# Schematics.net
KiCad netlist of a schematic drawn in EAGLE
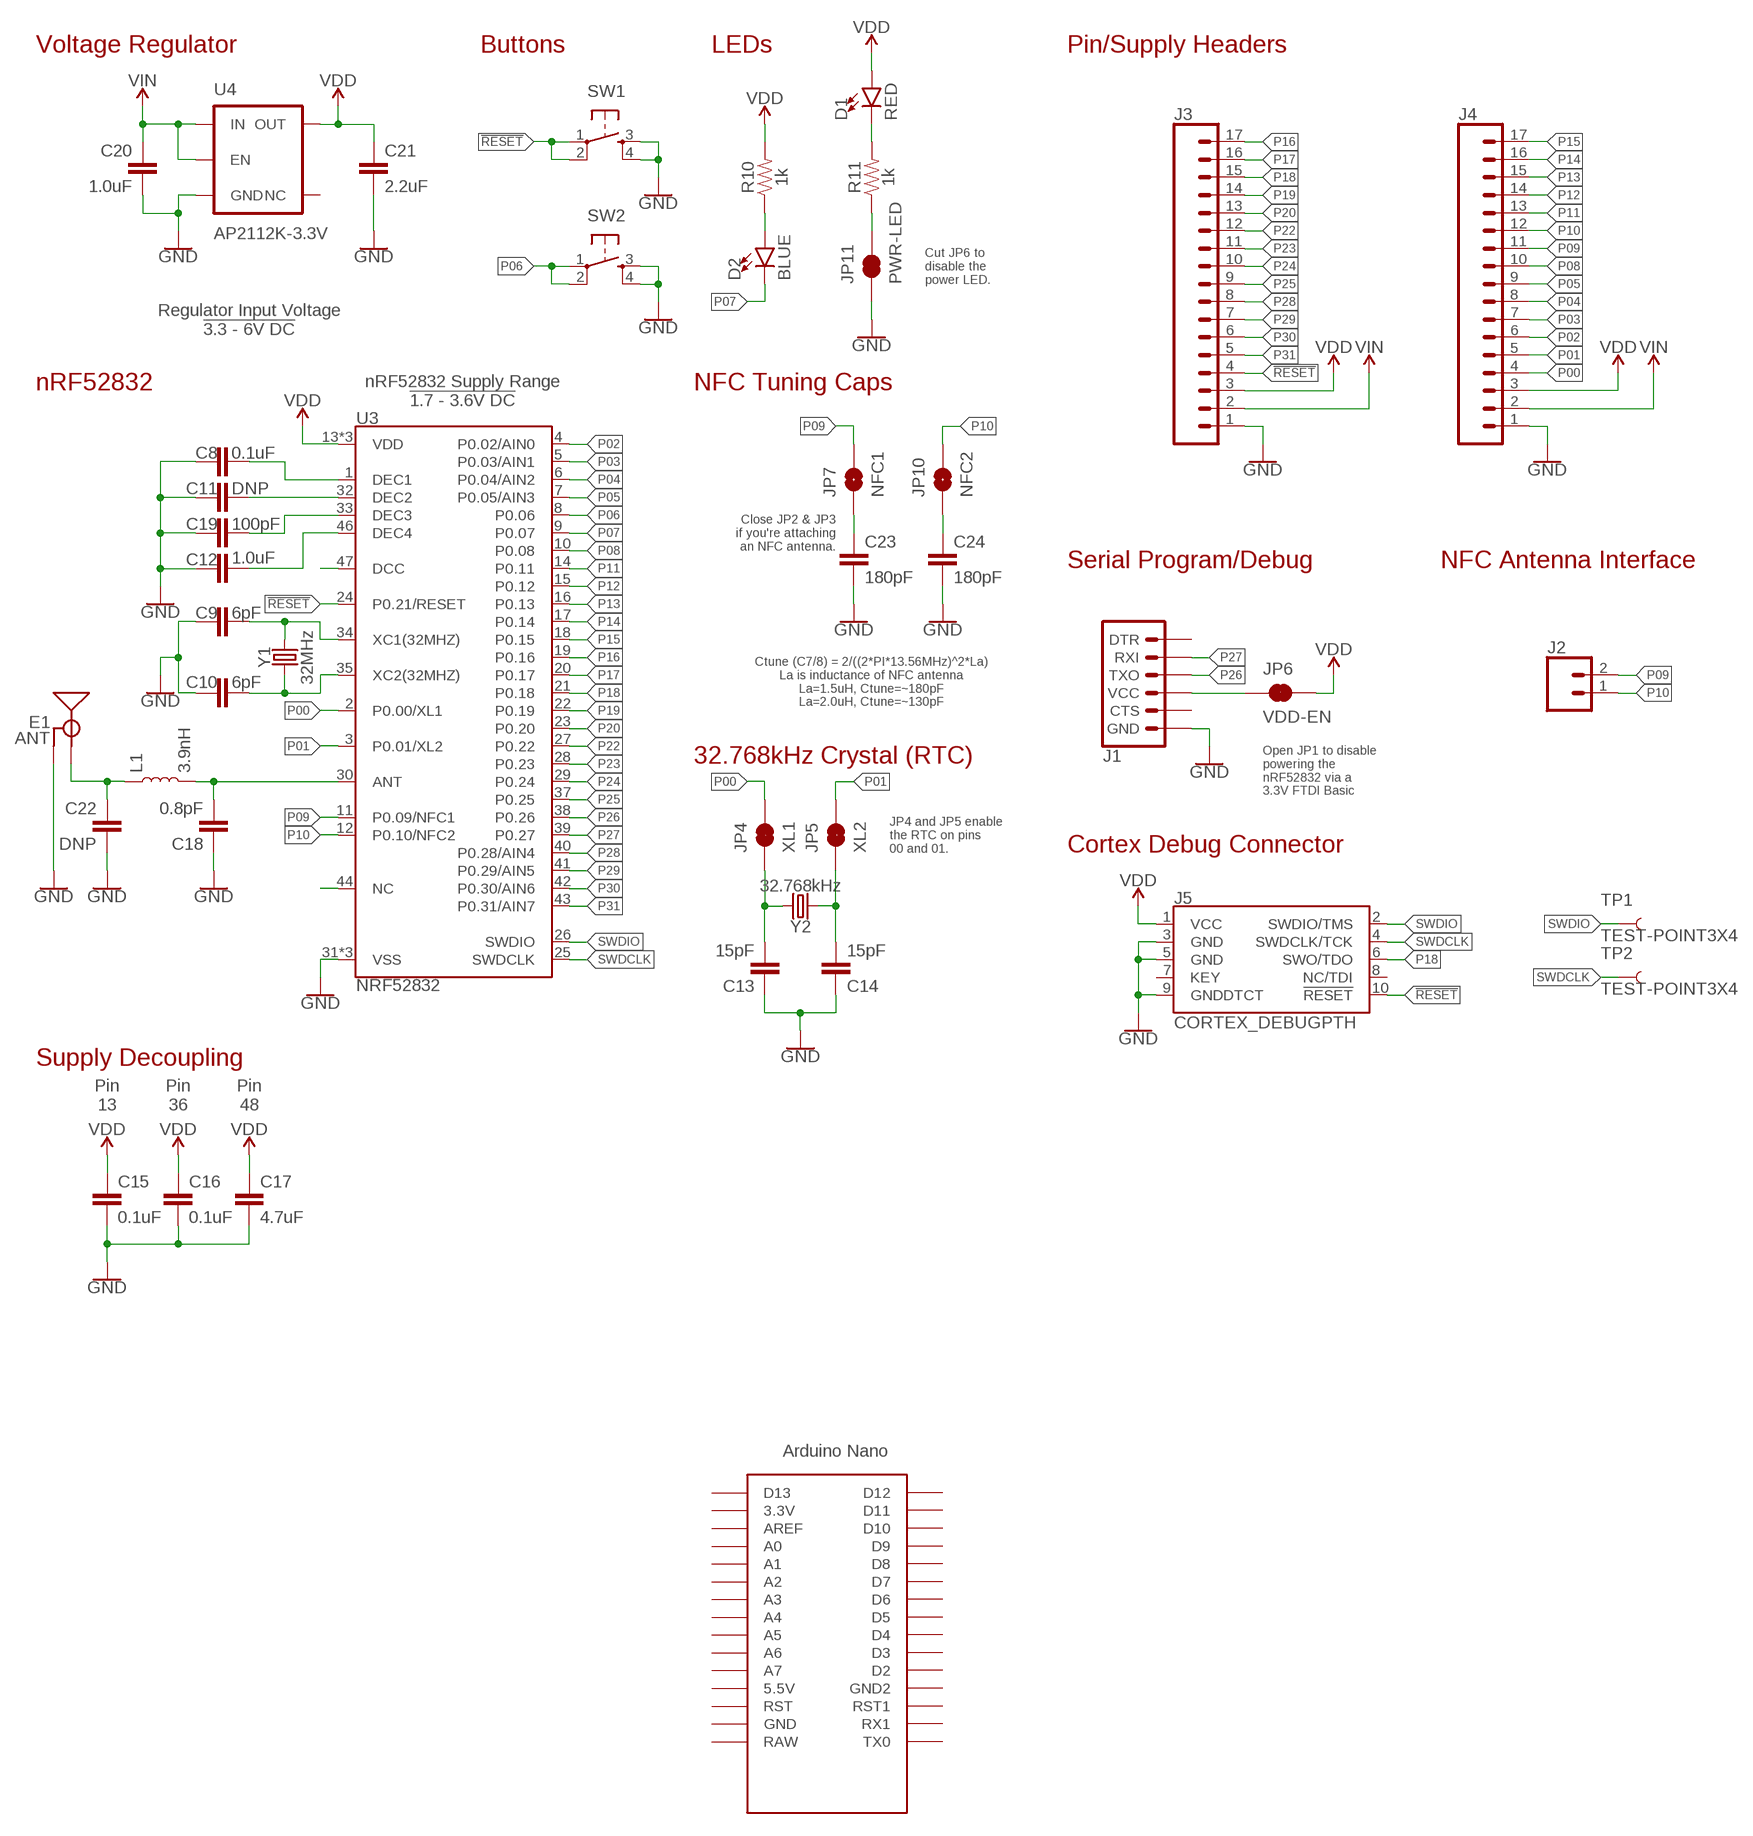
[diagram p0: schematic, sheet 1, part 1 of 2]
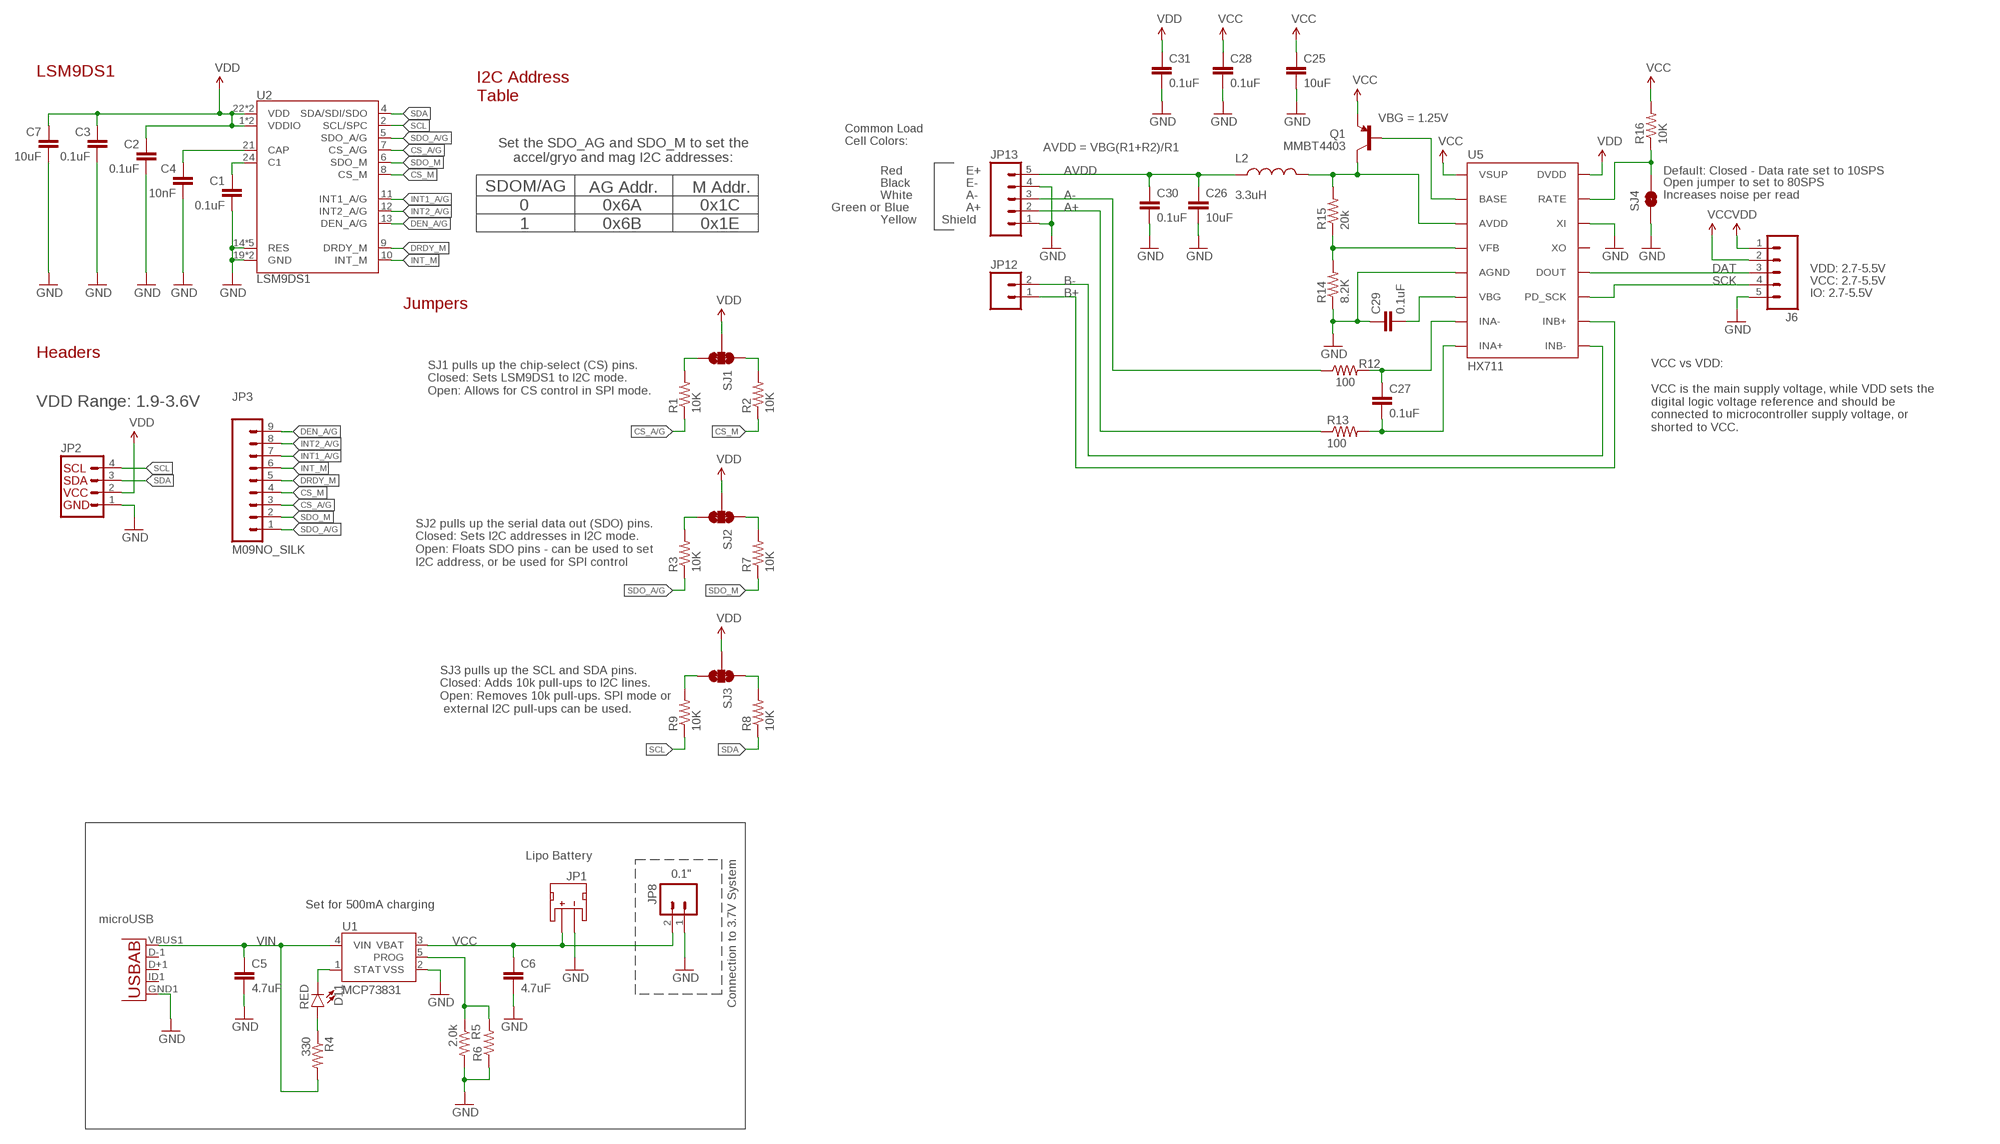
[diagram p1: schematic, sheet 1, part 2 of 2]

(export (version "E")
  (design (tool "Eeschema 10.0.6"))
  (components
    (comp (ref "C1")
      (value "0.1uF")
      (footprint "eagle-import:0603-CAP@1")
      (libsource (lib "eagle-import") (part "0.1UF-25V(+80/-20%)(0603)"))
    )
    (comp (ref "C2")
      (value "0.1uF")
      (footprint "eagle-import:0603-CAP@1")
      (libsource (lib "eagle-import") (part "0.1UF-25V(+80/-20%)(0603)"))
    )
    (comp (ref "C3")
      (value "0.1uF")
      (footprint "eagle-import:0603-CAP@1")
      (libsource (lib "eagle-import") (part "0.1UF-25V(+80/-20%)(0603)"))
    )
    (comp (ref "C4")
      (value "10nF")
      (footprint "eagle-import:0603-CAP@1")
      (libsource (lib "eagle-import") (part "10NF/10000PF-50V-10%(0603)"))
    )
    (comp (ref "C5")
      (value "4.7uF")
      (footprint "eagle-import:0603-CAP@1")
      (libsource (lib "eagle-import") (part "4.7UF-6.3V-10%(0603)0603"))
    )
    (comp (ref "C6")
      (value "4.7uF")
      (footprint "eagle-import:0603-CAP@1")
      (libsource (lib "eagle-import") (part "4.7UF-6.3V-10%(0603)0603"))
    )
    (comp (ref "C7")
      (value "10uF")
      (footprint "eagle-import:0603-CAP@1")
      (libsource (lib "eagle-import") (part "10UF-6.3V-20%(0603)"))
    )
    (comp (ref "C8")
      (value "0.1uF")
      (footprint "eagle-import:0402")
      (libsource (lib "eagle-import") (part "0.1UF-0402-16V-10%"))
    )
    (comp (ref "C9")
      (value "6pF")
      (footprint "eagle-import:0402")
      (libsource (lib "eagle-import") (part "6PF-0402-50V-0.5%"))
    )
    (comp (ref "C10")
      (value "6pF")
      (footprint "eagle-import:0402")
      (libsource (lib "eagle-import") (part "6PF-0402-50V-0.5%"))
    )
    (comp (ref "C11")
      (value "DNP")
      (footprint "eagle-import:0402")
      (libsource (lib "eagle-import") (part "CAP0402"))
    )
    (comp (ref "C12")
      (value "1.0uF")
      (footprint "eagle-import:0402")
      (libsource (lib "eagle-import") (part "1.0UF-0402-16V-10%"))
    )
    (comp (ref "C13")
      (value "15pF")
      (footprint "eagle-import:0402")
      (libsource (lib "eagle-import") (part "15PF-0402-50V-5%"))
    )
    (comp (ref "C14")
      (value "15pF")
      (footprint "eagle-import:0402")
      (libsource (lib "eagle-import") (part "15PF-0402-50V-5%"))
    )
    (comp (ref "C15")
      (value "0.1uF")
      (footprint "eagle-import:0402")
      (libsource (lib "eagle-import") (part "0.1UF-0402-16V-10%"))
    )
    (comp (ref "C16")
      (value "0.1uF")
      (footprint "eagle-import:0402")
      (libsource (lib "eagle-import") (part "0.1UF-0402-16V-10%"))
    )
    (comp (ref "C17")
      (value "4.7uF")
      (footprint "eagle-import:0603")
      (libsource (lib "eagle-import") (part "4.7UF0603"))
    )
    (comp (ref "C18")
      (value "0.8pF")
      (footprint "eagle-import:0402")
      (libsource (lib "eagle-import") (part "0.8PF-0402-50V-0.1PF"))
    )
    (comp (ref "C19")
      (value "100pF")
      (footprint "eagle-import:0402")
      (libsource (lib "eagle-import") (part "100PF-0402-50V-5%"))
    )
    (comp (ref "C20")
      (value "1.0uF")
      (footprint "eagle-import:0603")
      (libsource (lib "eagle-import") (part "1.0UF-0603-16V-10%"))
    )
    (comp (ref "C21")
      (value "2.2uF")
      (footprint "eagle-import:0603")
      (libsource (lib "eagle-import") (part "2.2UF-0603-10V-20%"))
    )
    (comp (ref "C22")
      (value "DNP")
      (footprint "eagle-import:0402")
      (libsource (lib "eagle-import") (part "CAP0402"))
    )
    (comp (ref "C23")
      (value "180pF")
      (footprint "eagle-import:0603")
      (libsource (lib "eagle-import") (part "180PF-0603-50V-5%"))
    )
    (comp (ref "C24")
      (value "180pF")
      (footprint "eagle-import:0603")
      (libsource (lib "eagle-import") (part "180PF-0603-50V-5%"))
    )
    (comp (ref "C25")
      (value "10uF")
      (footprint "eagle-import:1210")
      (libsource (lib "eagle-import") (part "10UF50V20%(1210)"))
    )
    (comp (ref "C26")
      (value "10uF")
      (footprint "eagle-import:1210")
      (libsource (lib "eagle-import") (part "10UF50V20%(1210)"))
    )
    (comp (ref "C27")
      (value "0.1uF")
      (footprint "eagle-import:0603-CAP")
      (libsource (lib "eagle-import") (part "0.1UF-25V-5%(0603)"))
    )
    (comp (ref "C28")
      (value "0.1uF")
      (footprint "eagle-import:0603-CAP")
      (libsource (lib "eagle-import") (part "0.1UF-25V-5%(0603)"))
    )
    (comp (ref "C29")
      (value "0.1uF")
      (footprint "eagle-import:0603-CAP")
      (libsource (lib "eagle-import") (part "0.1UF-25V-5%(0603)"))
    )
    (comp (ref "C30")
      (value "0.1uF")
      (footprint "eagle-import:0603-CAP")
      (libsource (lib "eagle-import") (part "0.1UF-25V-5%(0603)"))
    )
    (comp (ref "C31")
      (value "0.1uF")
      (footprint "eagle-import:0603-CAP")
      (libsource (lib "eagle-import") (part "0.1UF-25V-5%(0603)"))
    )
    (comp (ref "D1")
      (value "RED")
      (footprint "eagle-import:LED-0603")
      (libsource (lib "eagle-import") (part "LED-RED0603"))
    )
    (comp (ref "D2")
      (value "BLUE")
      (footprint "eagle-import:LED-0603")
      (libsource (lib "eagle-import") (part "LED-BLUE0603"))
    )
    (comp (ref "D11")
      (value "RED")
      (footprint "eagle-import:LED-0603")
      (libsource (lib "eagle-import") (part "LED-RED0603"))
    )
    (comp (ref "E1")
      (value "ANT")
      (footprint "eagle-import:TRACE_ANTENNA_2.4GHZ_15.2MM")
      (libsource (lib "eagle-import") (part "ANTENNA-GROUNDEDTRACE-15.2MM"))
    )
    (comp (ref "J1")
      (value "ARDUINO_SERIAL_PROGRAMPTH")
      (footprint "eagle-import:1X06")
      (libsource (lib "eagle-import") (part "ARDUINO_SERIAL_PROGRAMPTH"))
    )
    (comp (ref "J2")
      (value "CONN_02PTH")
      (footprint "eagle-import:1X02@2")
      (libsource (lib "eagle-import") (part "CONN_02PTH"))
    )
    (comp (ref "J3")
      (value "CONN_17")
      (footprint "eagle-import:1X17")
      (libsource (lib "eagle-import") (part "CONN_17"))
    )
    (comp (ref "J4")
      (value "CONN_17")
      (footprint "eagle-import:1X17")
      (libsource (lib "eagle-import") (part "CONN_17"))
    )
    (comp (ref "J5")
      (value "CORTEX_DEBUGPTH")
      (footprint "eagle-import:2X5-PTH-1.27MM")
      (libsource (lib "eagle-import") (part "CORTEX_DEBUGPTH"))
    )
    (comp (ref "J6")
      (value "M05PTH")
      (footprint "eagle-import:1X05")
      (libsource (lib "eagle-import") (part "M05PTH"))
    )
    (comp (ref "JP1")
      (value "JST")
      (footprint "eagle-import:JST-2-SMD@1")
      (libsource (lib "eagle-import") (part "JST_2MM_MALE"))
    )
    (comp (ref "JP2")
      (value "I2C_STANDARD_NO_SILK")
      (footprint "eagle-import:1X04_NO_SILK")
      (libsource (lib "eagle-import") (part "I2C_STANDARD_NO_SILK"))
    )
    (comp (ref "JP3")
      (value "M09NO_SILK")
      (footprint "eagle-import:1X09_NO_SILK")
      (libsource (lib "eagle-import") (part "M09NO_SILK"))
    )
    (comp (ref "JP4")
      (value "XL1")
      (footprint "eagle-import:PAD-JUMPER-2-NC_BY_TRACE_YES_SILK")
      (libsource (lib "eagle-import") (part "JUMPER-PAD-2-NC_BY_TRACE"))
    )
    (comp (ref "JP5")
      (value "XL2")
      (footprint "eagle-import:PAD-JUMPER-2-NC_BY_TRACE_YES_SILK")
      (libsource (lib "eagle-import") (part "JUMPER-PAD-2-NC_BY_TRACE"))
    )
    (comp (ref "JP6")
      (value "VDD-EN")
      (footprint "eagle-import:SMT-JUMPER_2_NC_TRACE_SILK")
      (libsource (lib "eagle-import") (part "JUMPER-SMT_2_NC_TRACE_SILK"))
    )
    (comp (ref "JP7")
      (value "NFC1")
      (footprint "eagle-import:SMT-JUMPER_2_NO_SILK")
      (libsource (lib "eagle-import") (part "JUMPER-SMT_2_NO_SILK"))
    )
    (comp (ref "JP8")
      (value "M02PTH")
      (footprint "eagle-import:1X02")
      (libsource (lib "eagle-import") (part "M02PTH"))
    )
    (comp (ref "JP9")
      (value "Micro USB")
      (footprint "eagle-import:USB-AB-MICRO-SMD_V03")
      (libsource (lib "eagle-import") (part "USB-ABCONN-11794"))
    )
    (comp (ref "JP10")
      (value "NFC2")
      (footprint "eagle-import:SMT-JUMPER_2_NO_SILK")
      (libsource (lib "eagle-import") (part "JUMPER-SMT_2_NO_SILK"))
    )
    (comp (ref "JP11")
      (value "PWR-LED")
      (footprint "eagle-import:PAD-JUMPER-2-NC_BY_TRACE_YES_SILK")
      (libsource (lib "eagle-import") (part "JUMPER-PAD-2-NC_BY_TRACE"))
    )
    (comp (ref "JP12")
      (value "M02PTH")
      (footprint "eagle-import:1X02")
      (libsource (lib "eagle-import") (part "M02PTH"))
    )
    (comp (ref "JP13")
      (value "M05PTH")
      (footprint "eagle-import:1X05")
      (libsource (lib "eagle-import") (part "M05PTH"))
    )
    (comp (ref "L1")
      (value "3.9nH")
      (footprint "eagle-import:0402")
      (libsource (lib "eagle-import") (part "INDUCTOR-0402-3.9NH"))
    )
    (comp (ref "L2")
      (value "3.3uH")
      (footprint "eagle-import:0805")
      (libsource (lib "eagle-import") (part "INDUCTOR0805-IND"))
    )
    (comp (ref "Q1")
      (value "MMBT4403")
      (footprint "eagle-import:SOT23-3")
      (libsource (lib "eagle-import") (part "TRANSISTOR_PNPMMBT4403"))
    )
    (comp (ref "R1")
      (value "10K")
      (footprint "eagle-import:0603-RES")
      (libsource (lib "eagle-import") (part "10KOHM-1/10W-1%(0603)0603"))
    )
    (comp (ref "R2")
      (value "10K")
      (footprint "eagle-import:0603-RES")
      (libsource (lib "eagle-import") (part "10KOHM-1/10W-1%(0603)0603"))
    )
    (comp (ref "R3")
      (value "10K")
      (footprint "eagle-import:0603-RES")
      (libsource (lib "eagle-import") (part "10KOHM-1/10W-1%(0603)0603"))
    )
    (comp (ref "R4")
      (value "330")
      (footprint "eagle-import:0603-RES@1")
      (libsource (lib "eagle-import") (part "330OHM1/10W1%(0603)"))
    )
    (comp (ref "R5")
      (value "2.0k")
      (footprint "eagle-import:0603-RES@1")
      (libsource (lib "eagle-import") (part "2.0KOHM1/10W5%(0603)"))
    )
    (comp (ref "R6")
      (value "RESISTORPTH-1/4W-VERT-KIT")
      (footprint "eagle-import:AXIAL-0.1EZ")
      (libsource (lib "eagle-import") (part "RESISTORPTH-1/4W-VERT-KIT"))
    )
    (comp (ref "R7")
      (value "10K")
      (footprint "eagle-import:0603-RES")
      (libsource (lib "eagle-import") (part "10KOHM-1/10W-1%(0603)0603"))
    )
    (comp (ref "R8")
      (value "10K")
      (footprint "eagle-import:0603-RES")
      (libsource (lib "eagle-import") (part "10KOHM-1/10W-1%(0603)0603"))
    )
    (comp (ref "R9")
      (value "10K")
      (footprint "eagle-import:0603-RES")
      (libsource (lib "eagle-import") (part "10KOHM-1/10W-1%(0603)0603"))
    )
    (comp (ref "R10")
      (value "1k")
      (footprint "eagle-import:0603")
      (libsource (lib "eagle-import") (part "1KOHM-0603-1/10W-1%"))
    )
    (comp (ref "R11")
      (value "1k")
      (footprint "eagle-import:0603")
      (libsource (lib "eagle-import") (part "1KOHM-0603-1/10W-1%"))
    )
    (comp (ref "R12")
      (value "100")
      (footprint "eagle-import:0603-RES")
      (libsource (lib "eagle-import") (part "100OHM-1/10W-1%(0603)"))
    )
    (comp (ref "R13")
      (value "100")
      (footprint "eagle-import:0603-RES")
      (libsource (lib "eagle-import") (part "100OHM-1/10W-1%(0603)"))
    )
    (comp (ref "R14")
      (value "8.2K")
      (footprint "eagle-import:0603-RES")
      (libsource (lib "eagle-import") (part "8.2KOHM-1/10W-5%(0603)"))
    )
    (comp (ref "R15")
      (value "20k")
      (footprint "eagle-import:0603-RES")
      (libsource (lib "eagle-import") (part "20KOHM1/10W1%(0603)"))
    )
    (comp (ref "R16")
      (value "10K")
      (footprint "eagle-import:0603-RES")
      (libsource (lib "eagle-import") (part "10KOHM-1/10W-1%(0603)0603"))
    )
    (comp (ref "SJ1")
      (value "JUMPER-PAD-3-NC_BY_TRACE")
      (footprint "eagle-import:PAD-JUMPER-3-3OF3_NC_BY_TRACE_YES_SILK_FULL_BOX")
      (libsource (lib "eagle-import") (part "JUMPER-PAD-3-NC_BY_TRACE"))
    )
    (comp (ref "SJ2")
      (value "JUMPER-PAD-3-NC_BY_TRACE")
      (footprint "eagle-import:PAD-JUMPER-3-3OF3_NC_BY_TRACE_YES_SILK_FULL_BOX")
      (libsource (lib "eagle-import") (part "JUMPER-PAD-3-NC_BY_TRACE"))
    )
    (comp (ref "SJ3")
      (value "JUMPER-PAD-3-NC_BY_TRACE")
      (footprint "eagle-import:PAD-JUMPER-3-3OF3_NC_BY_TRACE_YES_SILK_FULL_BOX")
      (libsource (lib "eagle-import") (part "JUMPER-PAD-3-NC_BY_TRACE"))
    )
    (comp (ref "SJ4")
      (value "JUMPER-PAD-2-NC_BY_TRACE")
      (footprint "eagle-import:PAD-JUMPER-2-NC_BY_TRACE_YES_SILK")
      (libsource (lib "eagle-import") (part "SparkFun-Passives_JUMPER-PAD-2-NC_BY_TRACE"))
    )
    (comp (ref "SW1")
      (value "SWITCH_SPST_4_PINRECT")
      (footprint "eagle-import:TACTILE_SWITCH_SMD_4.6X2.8MM")
      (libsource (lib "eagle-import") (part "SWITCH_SPST_4_PINRECT"))
    )
    (comp (ref "SW2")
      (value "SWITCH_SPST_4_PINRECT")
      (footprint "eagle-import:TACTILE_SWITCH_SMD_4.6X2.8MM")
      (libsource (lib "eagle-import") (part "SWITCH_SPST_4_PINRECT"))
    )
    (comp (ref "TP1")
      (value "TEST-POINT3X4")
      (footprint "eagle-import:PAD.03X.04")
      (libsource (lib "eagle-import") (part "TEST-POINT3X4"))
    )
    (comp (ref "TP2")
      (value "TEST-POINT3X4")
      (footprint "eagle-import:PAD.03X.04")
      (libsource (lib "eagle-import") (part "TEST-POINT3X4"))
    )
    (comp (ref "U$1")
      (value "NANO")
      (footprint "eagle-import:NANO")
      (libsource (lib "eagle-import") (part "NANO"))
    )
    (comp (ref "U1")
      (value "MCP73831")
      (footprint "eagle-import:SOT23-5@1")
      (libsource (lib "eagle-import") (part "MCP73831"))
    )
    (comp (ref "U2")
      (value "LSM9DS1")
      (footprint "eagle-import:LGA24-8X4")
      (libsource (lib "eagle-import") (part "LSM9DS1"))
    )
    (comp (ref "U3")
      (value "NRF52832")
      (footprint "eagle-import:QFN48-6X6MM")
      (libsource (lib "eagle-import") (part "NRF52832"))
    )
    (comp (ref "U4")
      (value "AP2112K-3.3V")
      (footprint "eagle-import:SOT23-5")
      (libsource (lib "eagle-import") (part "V_REG_AP2112K-3.3V"))
    )
    (comp (ref "U5")
      (value "HX711")
      (footprint "eagle-import:SO16")
      (libsource (lib "eagle-import") (part "HX711HX711"))
    )
    (comp (ref "Y1")
      (value "32MHz")
      (footprint "eagle-import:CRYSTAL-SMD-2.0X1.6MM")
      (libsource (lib "eagle-import") (part "CRYSTAL-32MHZ-SMD-2.0X1.6MM"))
    )
    (comp (ref "Y2")
      (value "32.768kHz")
      (footprint "eagle-import:CRYSTAL-SMD-3.2X1.5MM")
      (libsource (lib "eagle-import") (part "CRYSTAL-32.768KHZSMD-3.2X1.5"))
    )
  )
  (nets
    (net (code "1") (name "/A+") (class "Default")
      (node (ref "JP13") (pin "2") (pinfunction "2_2") (pintype "passive"))
      (node (ref "R13") (pin "1") (pinfunction "1_1") (pintype "passive"))
    )
    (net (code "2") (name "/A-") (class "Default")
      (node (ref "JP13") (pin "3") (pinfunction "3_3") (pintype "passive"))
      (node (ref "R12") (pin "1") (pinfunction "1_1") (pintype "passive"))
    )
    (net (code "3") (name "/AVDD") (class "Default")
      (node (ref "C26") (pin "1") (pinfunction "1_1") (pintype "passive"))
      (node (ref "C30") (pin "1") (pinfunction "1_1") (pintype "passive"))
      (node (ref "JP13") (pin "5") (pinfunction "5_5") (pintype "passive"))
      (node (ref "L2") (pin "1") (pinfunction "1_1") (pintype "passive"))
    )
    (net (code "4") (name "/B+") (class "Default")
      (node (ref "JP12") (pin "1") (pinfunction "1_1") (pintype "passive"))
      (node (ref "U5") (pin "10") (pinfunction "INB+_10") (pintype "bidirectional"))
    )
    (net (code "5") (name "/B-") (class "Default")
      (node (ref "JP12") (pin "2") (pinfunction "2_2") (pintype "passive"))
      (node (ref "U5") (pin "9") (pinfunction "INB-_9") (pintype "bidirectional"))
    )
    (net (code "6") (name "/DAT") (class "Default")
      (node (ref "J6") (pin "3") (pinfunction "3_3") (pintype "passive"))
      (node (ref "U5") (pin "12") (pinfunction "DOUT_12") (pintype "bidirectional"))
    )
    (net (code "7") (name "/SCK") (class "Default")
      (node (ref "J6") (pin "4") (pinfunction "4_4") (pintype "passive"))
      (node (ref "U5") (pin "11") (pinfunction "PD_SCK_11") (pintype "bidirectional"))
    )
    (net (code "8") (name "/~{RESET}") (class "Default")
      (node (ref "J3") (pin "4") (pinfunction "4_4") (pintype "passive"))
      (node (ref "J5") (pin "10") (pinfunction "~{RESET}_10") (pintype "bidirectional"))
      (node (ref "SW1") (pin "1") (pinfunction "1_1") (pintype "passive"))
      (node (ref "SW1") (pin "2") (pinfunction "2_2") (pintype "passive"))
      (node (ref "U3") (pin "24") (pinfunction "P0.21/RESET_24") (pintype "bidirectional"))
    )
    (net (code "9") (name "CS_A{slash}G") (class "Default")
      (node (ref "JP3") (pin "3") (pinfunction "3_3") (pintype "passive"))
      (node (ref "R1") (pin "1") (pinfunction "1_1") (pintype "passive"))
      (node (ref "U2") (pin "7") (pinfunction "CS_A/G_7") (pintype "bidirectional"))
    )
    (net (code "10") (name "CS_M") (class "Default")
      (node (ref "JP3") (pin "4") (pinfunction "4_4") (pintype "passive"))
      (node (ref "R2") (pin "1") (pinfunction "1_1") (pintype "passive"))
      (node (ref "U2") (pin "8") (pinfunction "CS_M_8") (pintype "bidirectional"))
    )
    (net (code "11") (name "DEN_A{slash}G") (class "Default")
      (node (ref "JP3") (pin "9") (pinfunction "9_9") (pintype "passive"))
      (node (ref "U2") (pin "13") (pinfunction "DEN_A/G_13") (pintype "bidirectional"))
    )
    (net (code "12") (name "DRDY_M") (class "Default")
      (node (ref "JP3") (pin "5") (pinfunction "5_5") (pintype "passive"))
      (node (ref "U2") (pin "9") (pinfunction "DRDY_M_9") (pintype "bidirectional"))
    )
    (net (code "13") (name "GND") (class "Default")
      (node (ref "C1") (pin "2") (pinfunction "2_2") (pintype "passive"))
      (node (ref "C10") (pin "2") (pinfunction "2_2") (pintype "passive"))
      (node (ref "C11") (pin "1") (pinfunction "1_1") (pintype "passive"))
      (node (ref "C12") (pin "1") (pinfunction "1_1") (pintype "passive"))
      (node (ref "C13") (pin "1") (pinfunction "1_1") (pintype "passive"))
      (node (ref "C14") (pin "1") (pinfunction "1_1") (pintype "passive"))
      (node (ref "C15") (pin "2") (pinfunction "2_2") (pintype "passive"))
      (node (ref "C16") (pin "2") (pinfunction "2_2") (pintype "passive"))
      (node (ref "C17") (pin "2") (pinfunction "2_2") (pintype "passive"))
      (node (ref "C18") (pin "1") (pinfunction "1_1") (pintype "passive"))
      (node (ref "C19") (pin "1") (pinfunction "1_1") (pintype "passive"))
      (node (ref "C2") (pin "2") (pinfunction "2_2") (pintype "passive"))
      (node (ref "C20") (pin "2") (pinfunction "2_2") (pintype "passive"))
      (node (ref "C21") (pin "2") (pinfunction "2_2") (pintype "passive"))
      (node (ref "C22") (pin "2") (pinfunction "2_2") (pintype "passive"))
      (node (ref "C23") (pin "2") (pinfunction "2_2") (pintype "passive"))
      (node (ref "C24") (pin "2") (pinfunction "2_2") (pintype "passive"))
      (node (ref "C25") (pin "2") (pinfunction "2_2") (pintype "passive"))
      (node (ref "C26") (pin "2") (pinfunction "2_2") (pintype "passive"))
      (node (ref "C28") (pin "2") (pinfunction "2_2") (pintype "passive"))
      (node (ref "C29") (pin "1") (pinfunction "1_1") (pintype "passive"))
      (node (ref "C3") (pin "2") (pinfunction "2_2") (pintype "passive"))
      (node (ref "C30") (pin "2") (pinfunction "2_2") (pintype "passive"))
      (node (ref "C31") (pin "2") (pinfunction "2_2") (pintype "passive"))
      (node (ref "C4") (pin "2") (pinfunction "2_2") (pintype "passive"))
      (node (ref "C5") (pin "2") (pinfunction "2_2") (pintype "passive"))
      (node (ref "C6") (pin "2") (pinfunction "2_2") (pintype "passive"))
      (node (ref "C7") (pin "2") (pinfunction "2_2") (pintype "passive"))
      (node (ref "C8") (pin "1") (pinfunction "1_1") (pintype "passive"))
      (node (ref "C9") (pin "1") (pinfunction "1_1") (pintype "passive"))
      (node (ref "E1") (pin "GND") (pinfunction "GND_GND") (pintype "bidirectional"))
      (node (ref "J1") (pin "6") (pinfunction "GND_6") (pintype "passive"))
      (node (ref "J3") (pin "1") (pinfunction "1_1") (pintype "passive"))
      (node (ref "J4") (pin "1") (pinfunction "1_1") (pintype "passive"))
      (node (ref "J5") (pin "3") (pinfunction "GND_3") (pintype "bidirectional"))
      (node (ref "J5") (pin "5") (pinfunction "GND_5") (pintype "bidirectional"))
      (node (ref "J5") (pin "9") (pinfunction "GNDDTCT_9") (pintype "bidirectional"))
      (node (ref "J6") (pin "5") (pinfunction "5_5") (pintype "passive"))
      (node (ref "JP1") (pin "1") (pinfunction "-_1") (pintype "bidirectional"))
      (node (ref "JP11") (pin "1") (pinfunction "1_1") (pintype "passive"))
      (node (ref "JP13") (pin "1") (pinfunction "1_1") (pintype "passive"))
      (node (ref "JP13") (pin "4") (pinfunction "4_4") (pintype "passive"))
      (node (ref "JP2") (pin "1") (pinfunction "1_1") (pintype "passive"))
      (node (ref "JP8") (pin "1") (pinfunction "1_1") (pintype "passive"))
      (node (ref "JP9") (pin "GND1") (pinfunction "GND_GND1") (pintype "bidirectional"))
      (node (ref "R14") (pin "1") (pinfunction "1_1") (pintype "passive"))
      (node (ref "R5") (pin "2") (pinfunction "2_2") (pintype "passive"))
      (node (ref "R6") (pin "P$1") (pinfunction "1_P$1") (pintype "passive"))
      (node (ref "SJ4") (pin "1") (pinfunction "1_1") (pintype "passive"))
      (node (ref "SW1") (pin "3") (pinfunction "3_3") (pintype "passive"))
      (node (ref "SW1") (pin "4") (pinfunction "4_4") (pintype "passive"))
      (node (ref "SW2") (pin "3") (pinfunction "3_3") (pintype "passive"))
      (node (ref "SW2") (pin "4") (pinfunction "4_4") (pintype "passive"))
      (node (ref "U1") (pin "2") (pinfunction "VSS_2") (pintype "power_in"))
      (node (ref "U2") (pin "14") (pinfunction "RES_14") (pintype "bidirectional"))
      (node (ref "U2") (pin "15") (pinfunction "RES_15") (pintype "bidirectional"))
      (node (ref "U2") (pin "16") (pinfunction "RES_16") (pintype "bidirectional"))
      (node (ref "U2") (pin "17") (pinfunction "RES_17") (pintype "bidirectional"))
      (node (ref "U2") (pin "18") (pinfunction "RES_18") (pintype "bidirectional"))
      (node (ref "U2") (pin "19") (pinfunction "GND_19") (pintype "bidirectional"))
      (node (ref "U2") (pin "20") (pinfunction "GND_20") (pintype "bidirectional"))
      (node (ref "U3") (pin "31") (pinfunction "VSS_31") (pintype "bidirectional"))
      (node (ref "U3") (pin "45") (pinfunction "VSS_45") (pintype "bidirectional"))
      (node (ref "U3") (pin "EP") (pinfunction "VSS_EP") (pintype "bidirectional"))
      (node (ref "U4") (pin "2") (pinfunction "GND_2") (pintype "input"))
      (node (ref "U5") (pin "14") (pinfunction "XI_14") (pintype "bidirectional"))
      (node (ref "U5") (pin "5") (pinfunction "AGND_5") (pintype "bidirectional"))
    )
    (net (code "14") (name "INT1_A{slash}G") (class "Default")
      (node (ref "JP3") (pin "7") (pinfunction "7_7") (pintype "passive"))
      (node (ref "U2") (pin "11") (pinfunction "INT1_A/G_11") (pintype "bidirectional"))
    )
    (net (code "15") (name "INT2_A{slash}G") (class "Default")
      (node (ref "JP3") (pin "8") (pinfunction "8_8") (pintype "passive"))
      (node (ref "U2") (pin "12") (pinfunction "INT2_A/G_12") (pintype "bidirectional"))
    )
    (net (code "16") (name "INT_M") (class "Default")
      (node (ref "JP3") (pin "6") (pinfunction "6_6") (pintype "passive"))
      (node (ref "U2") (pin "10") (pinfunction "INT_M_10") (pintype "bidirectional"))
    )
    (net (code "17") (name "Net-(C23-Pad1)") (class "Default")
      (node (ref "C23") (pin "1") (pinfunction "1_1") (pintype "passive"))
      (node (ref "JP7") (pin "1") (pinfunction "1_1") (pintype "passive"))
    )
    (net (code "18") (name "Net-(C24-Pad1)") (class "Default")
      (node (ref "C24") (pin "1") (pinfunction "1_1") (pintype "passive"))
      (node (ref "JP10") (pin "1") (pinfunction "1_1") (pintype "passive"))
    )
    (net (code "19") (name "Net-(D1-PadC)") (class "Default")
      (node (ref "D1") (pin "C") (pinfunction "C_C") (pintype "passive"))
      (node (ref "R11") (pin "2") (pinfunction "2_2") (pintype "passive"))
    )
    (net (code "20") (name "Net-(D2-PadA)") (class "Default")
      (node (ref "D2") (pin "A") (pinfunction "A_A") (pintype "passive"))
      (node (ref "R10") (pin "1") (pinfunction "1_1") (pintype "passive"))
    )
    (net (code "21") (name "Net-(D11-PadA)") (class "Default")
      (node (ref "D11") (pin "A") (pinfunction "A_A") (pintype "passive"))
      (node (ref "R4") (pin "1") (pinfunction "1_1") (pintype "passive"))
    )
    (net (code "22") (name "Net-(E1-SIGNAL)") (class "Default")
      (node (ref "C22") (pin "1") (pinfunction "1_1") (pintype "passive"))
      (node (ref "E1") (pin "ANT") (pinfunction "SIGNAL_ANT") (pintype "bidirectional"))
      (node (ref "L1") (pin "1") (pinfunction "1_1") (pintype "passive"))
    )
    (net (code "23") (name "Net-(J1-VCC)") (class "Default")
      (node (ref "J1") (pin "4") (pinfunction "VCC_4") (pintype "passive"))
      (node (ref "JP6") (pin "1") (pinfunction "1_1") (pintype "passive"))
    )
    (net (code "24") (name "Net-(JP11-Pad2)") (class "Default")
      (node (ref "JP11") (pin "2") (pinfunction "2_2") (pintype "passive"))
      (node (ref "R11") (pin "1") (pinfunction "1_1") (pintype "passive"))
    )
    (net (code "25") (name "Net-(Q1-B)") (class "Default")
      (node (ref "Q1") (pin "1") (pinfunction "B_1") (pintype "passive"))
      (node (ref "U5") (pin "2") (pinfunction "BASE_2") (pintype "bidirectional"))
    )
    (net (code "26") (name "Net-(Q1-C)") (class "Default")
      (node (ref "L2") (pin "2") (pinfunction "2_2") (pintype "passive"))
      (node (ref "Q1") (pin "3") (pinfunction "C_3") (pintype "passive"))
      (node (ref "R15") (pin "2") (pinfunction "2_2") (pintype "passive"))
      (node (ref "U5") (pin "3") (pinfunction "AVDD_3") (pintype "bidirectional"))
    )
    (net (code "27") (name "Net-(R1-Pad2)") (class "Default")
      (node (ref "R1") (pin "2") (pinfunction "2_2") (pintype "passive"))
      (node (ref "SJ1") (pin "3") (pinfunction "3_3") (pintype "passive"))
    )
    (net (code "28") (name "Net-(R2-Pad2)") (class "Default")
      (node (ref "R2") (pin "2") (pinfunction "2_2") (pintype "passive"))
      (node (ref "SJ1") (pin "1") (pinfunction "1_1") (pintype "passive"))
    )
    (net (code "29") (name "Net-(R3-Pad2)") (class "Default")
      (node (ref "R3") (pin "2") (pinfunction "2_2") (pintype "passive"))
      (node (ref "SJ2") (pin "3") (pinfunction "3_3") (pintype "passive"))
    )
    (net (code "30") (name "Net-(R6-2)") (class "Default")
      (node (ref "R5") (pin "1") (pinfunction "1_1") (pintype "passive"))
      (node (ref "R6") (pin "P$2") (pinfunction "2_P$2") (pintype "passive"))
      (node (ref "U1") (pin "5") (pinfunction "PROG_5") (pintype "input"))
    )
    (net (code "31") (name "Net-(R7-Pad2)") (class "Default")
      (node (ref "R7") (pin "2") (pinfunction "2_2") (pintype "passive"))
      (node (ref "SJ2") (pin "1") (pinfunction "1_1") (pintype "passive"))
    )
    (net (code "32") (name "Net-(R8-Pad2)") (class "Default")
      (node (ref "R8") (pin "2") (pinfunction "2_2") (pintype "passive"))
      (node (ref "SJ3") (pin "1") (pinfunction "1_1") (pintype "passive"))
    )
    (net (code "33") (name "Net-(R9-Pad2)") (class "Default")
      (node (ref "R9") (pin "2") (pinfunction "2_2") (pintype "passive"))
      (node (ref "SJ3") (pin "3") (pinfunction "3_3") (pintype "passive"))
    )
    (net (code "34") (name "Net-(U1-STAT)") (class "Default")
      (node (ref "D11") (pin "C") (pinfunction "C_C") (pintype "passive"))
      (node (ref "U1") (pin "1") (pinfunction "STAT_1") (pintype "output"))
    )
    (net (code "35") (name "Net-(U2-C1)") (class "Default")
      (node (ref "C1") (pin "1") (pinfunction "1_1") (pintype "passive"))
      (node (ref "U2") (pin "24") (pinfunction "C1_24") (pintype "bidirectional"))
    )
    (net (code "36") (name "Net-(U2-CAP)") (class "Default")
      (node (ref "C4") (pin "1") (pinfunction "1_1") (pintype "passive"))
      (node (ref "U2") (pin "21") (pinfunction "CAP_21") (pintype "bidirectional"))
    )
    (net (code "37") (name "Net-(U3-ANT)") (class "Default")
      (node (ref "C18") (pin "2") (pinfunction "2_2") (pintype "passive"))
      (node (ref "L1") (pin "2") (pinfunction "2_2") (pintype "passive"))
      (node (ref "U3") (pin "30") (pinfunction "ANT_30") (pintype "bidirectional"))
    )
    (net (code "38") (name "Net-(U3-DEC1)") (class "Default")
      (node (ref "C8") (pin "2") (pinfunction "2_2") (pintype "passive"))
      (node (ref "U3") (pin "1") (pinfunction "DEC1_1") (pintype "bidirectional"))
    )
    (net (code "39") (name "Net-(U3-DEC2)") (class "Default")
      (node (ref "C11") (pin "2") (pinfunction "2_2") (pintype "passive"))
      (node (ref "U3") (pin "32") (pinfunction "DEC2_32") (pintype "bidirectional"))
    )
    (net (code "40") (name "Net-(U3-DEC3)") (class "Default")
      (node (ref "C19") (pin "2") (pinfunction "2_2") (pintype "passive"))
      (node (ref "U3") (pin "33") (pinfunction "DEC3_33") (pintype "bidirectional"))
    )
    (net (code "41") (name "Net-(U3-DEC4)") (class "Default")
      (node (ref "C12") (pin "2") (pinfunction "2_2") (pintype "passive"))
      (node (ref "U3") (pin "46") (pinfunction "DEC4_46") (pintype "bidirectional"))
    )
    (net (code "42") (name "Net-(U3-XC1(32MHZ))") (class "Default")
      (node (ref "C9") (pin "2") (pinfunction "2_2") (pintype "passive"))
      (node (ref "U3") (pin "34") (pinfunction "XC1(32MHZ)_34") (pintype "bidirectional"))
      (node (ref "Y1") (pin "3") (pinfunction "2_3") (pintype "passive"))
    )
    (net (code "43") (name "Net-(U3-XC2(32MHZ))") (class "Default")
      (node (ref "C10") (pin "1") (pinfunction "1_1") (pintype "passive"))
      (node (ref "U3") (pin "35") (pinfunction "XC2(32MHZ)_35") (pintype "bidirectional"))
      (node (ref "Y1") (pin "1") (pinfunction "1_1") (pintype "passive"))
    )
    (net (code "44") (name "Net-(U5-INA+)") (class "Default")
      (node (ref "C27") (pin "2") (pinfunction "2_2") (pintype "passive"))
      (node (ref "R13") (pin "2") (pinfunction "2_2") (pintype "passive"))
      (node (ref "U5") (pin "8") (pinfunction "INA+_8") (pintype "bidirectional"))
    )
    (net (code "45") (name "Net-(U5-INA-)") (class "Default")
      (node (ref "C27") (pin "1") (pinfunction "1_1") (pintype "passive"))
      (node (ref "R12") (pin "2") (pinfunction "2_2") (pintype "passive"))
      (node (ref "U5") (pin "7") (pinfunction "INA-_7") (pintype "bidirectional"))
    )
    (net (code "46") (name "Net-(U5-RATE)") (class "Default")
      (node (ref "R16") (pin "1") (pinfunction "1_1") (pintype "passive"))
      (node (ref "SJ4") (pin "2") (pinfunction "2_2") (pintype "passive"))
      (node (ref "U5") (pin "15") (pinfunction "RATE_15") (pintype "bidirectional"))
    )
    (net (code "47") (name "Net-(U5-VBG)") (class "Default")
      (node (ref "C29") (pin "2") (pinfunction "2_2") (pintype "passive"))
      (node (ref "U5") (pin "6") (pinfunction "VBG_6") (pintype "bidirectional"))
    )
    (net (code "48") (name "Net-(U5-VFB)") (class "Default")
      (node (ref "R14") (pin "2") (pinfunction "2_2") (pintype "passive"))
      (node (ref "R15") (pin "1") (pinfunction "1_1") (pintype "passive"))
      (node (ref "U5") (pin "4") (pinfunction "VFB_4") (pintype "bidirectional"))
    )
    (net (code "49") (name "Net-(Y2-1)") (class "Default")
      (node (ref "C14") (pin "2") (pinfunction "2_2") (pintype "passive"))
      (node (ref "JP5") (pin "1") (pinfunction "1_1") (pintype "passive"))
      (node (ref "Y2") (pin "P$1") (pinfunction "1_P$1") (pintype "passive"))
    )
    (net (code "50") (name "Net-(Y2-2)") (class "Default")
      (node (ref "C13") (pin "2") (pinfunction "2_2") (pintype "passive"))
      (node (ref "JP4") (pin "1") (pinfunction "1_1") (pintype "passive"))
      (node (ref "Y2") (pin "P$2") (pinfunction "2_P$2") (pintype "passive"))
    )
    (net (code "51") (name "P00") (class "Default")
      (node (ref "J4") (pin "4") (pinfunction "4_4") (pintype "passive"))
      (node (ref "JP4") (pin "2") (pinfunction "2_2") (pintype "passive"))
      (node (ref "U3") (pin "2") (pinfunction "P0.00/XL1_2") (pintype "bidirectional"))
    )
    (net (code "52") (name "P01") (class "Default")
      (node (ref "J4") (pin "5") (pinfunction "5_5") (pintype "passive"))
      (node (ref "JP5") (pin "2") (pinfunction "2_2") (pintype "passive"))
      (node (ref "U3") (pin "3") (pinfunction "P0.01/XL2_3") (pintype "bidirectional"))
    )
    (net (code "53") (name "P02") (class "Default")
      (node (ref "J4") (pin "6") (pinfunction "6_6") (pintype "passive"))
      (node (ref "U3") (pin "4") (pinfunction "P0.02/AIN0_4") (pintype "bidirectional"))
    )
    (net (code "54") (name "P03") (class "Default")
      (node (ref "J4") (pin "7") (pinfunction "7_7") (pintype "passive"))
      (node (ref "U3") (pin "5") (pinfunction "P0.03/AIN1_5") (pintype "bidirectional"))
    )
    (net (code "55") (name "P04") (class "Default")
      (node (ref "J4") (pin "8") (pinfunction "8_8") (pintype "passive"))
      (node (ref "U3") (pin "6") (pinfunction "P0.04/AIN2_6") (pintype "bidirectional"))
    )
    (net (code "56") (name "P05") (class "Default")
      (node (ref "J4") (pin "9") (pinfunction "9_9") (pintype "passive"))
      (node (ref "U3") (pin "7") (pinfunction "P0.05/AIN3_7") (pintype "bidirectional"))
    )
    (net (code "57") (name "P06") (class "Default")
      (node (ref "SW2") (pin "1") (pinfunction "1_1") (pintype "passive"))
      (node (ref "SW2") (pin "2") (pinfunction "2_2") (pintype "passive"))
      (node (ref "U3") (pin "8") (pinfunction "P0.06_8") (pintype "bidirectional"))
    )
    (net (code "58") (name "P07") (class "Default")
      (node (ref "D2") (pin "C") (pinfunction "C_C") (pintype "passive"))
      (node (ref "U3") (pin "9") (pinfunction "P0.07_9") (pintype "bidirectional"))
    )
    (net (code "59") (name "P08") (class "Default")
      (node (ref "J4") (pin "10") (pinfunction "10_10") (pintype "passive"))
      (node (ref "U3") (pin "10") (pinfunction "P0.08_10") (pintype "bidirectional"))
    )
    (net (code "60") (name "P09") (class "Default")
      (node (ref "J2") (pin "2") (pinfunction "2_2") (pintype "passive"))
      (node (ref "J4") (pin "11") (pinfunction "11_11") (pintype "passive"))
      (node (ref "JP7") (pin "2") (pinfunction "2_2") (pintype "passive"))
      (node (ref "U3") (pin "11") (pinfunction "P0.09/NFC1_11") (pintype "bidirectional"))
    )
    (net (code "61") (name "P10") (class "Default")
      (node (ref "J2") (pin "1") (pinfunction "1_1") (pintype "passive"))
      (node (ref "J4") (pin "12") (pinfunction "12_12") (pintype "passive"))
      (node (ref "JP10") (pin "2") (pinfunction "2_2") (pintype "passive"))
      (node (ref "U3") (pin "12") (pinfunction "P0.10/NFC2_12") (pintype "bidirectional"))
    )
    (net (code "62") (name "P11") (class "Default")
      (node (ref "J4") (pin "13") (pinfunction "13_13") (pintype "passive"))
      (node (ref "U3") (pin "14") (pinfunction "P0.11_14") (pintype "bidirectional"))
    )
    (net (code "63") (name "P12") (class "Default")
      (node (ref "J4") (pin "14") (pinfunction "14_14") (pintype "passive"))
      (node (ref "U3") (pin "15") (pinfunction "P0.12_15") (pintype "bidirectional"))
    )
    (net (code "64") (name "P13") (class "Default")
      (node (ref "J4") (pin "15") (pinfunction "15_15") (pintype "passive"))
      (node (ref "U3") (pin "16") (pinfunction "P0.13_16") (pintype "bidirectional"))
    )
    (net (code "65") (name "P14") (class "Default")
      (node (ref "J4") (pin "16") (pinfunction "16_16") (pintype "passive"))
      (node (ref "U3") (pin "17") (pinfunction "P0.14_17") (pintype "bidirectional"))
    )
    (net (code "66") (name "P15") (class "Default")
      (node (ref "J4") (pin "17") (pinfunction "17_17") (pintype "passive"))
      (node (ref "U3") (pin "18") (pinfunction "P0.15_18") (pintype "bidirectional"))
    )
    (net (code "67") (name "P16") (class "Default")
      (node (ref "J3") (pin "17") (pinfunction "17_17") (pintype "passive"))
      (node (ref "U3") (pin "19") (pinfunction "P0.16_19") (pintype "bidirectional"))
    )
    (net (code "68") (name "P17") (class "Default")
      (node (ref "J3") (pin "16") (pinfunction "16_16") (pintype "passive"))
      (node (ref "U3") (pin "20") (pinfunction "P0.17_20") (pintype "bidirectional"))
    )
    (net (code "69") (name "P18") (class "Default")
      (node (ref "J3") (pin "15") (pinfunction "15_15") (pintype "passive"))
      (node (ref "J5") (pin "6") (pinfunction "SWO/TDO_6") (pintype "bidirectional"))
      (node (ref "U3") (pin "21") (pinfunction "P0.18_21") (pintype "bidirectional"))
    )
    (net (code "70") (name "P19") (class "Default")
      (node (ref "J3") (pin "14") (pinfunction "14_14") (pintype "passive"))
      (node (ref "U3") (pin "22") (pinfunction "P0.19_22") (pintype "bidirectional"))
    )
    (net (code "71") (name "P20") (class "Default")
      (node (ref "J3") (pin "13") (pinfunction "13_13") (pintype "passive"))
      (node (ref "U3") (pin "23") (pinfunction "P0.20_23") (pintype "bidirectional"))
    )
    (net (code "72") (name "P22") (class "Default")
      (node (ref "J3") (pin "12") (pinfunction "12_12") (pintype "passive"))
      (node (ref "U3") (pin "27") (pinfunction "P0.22_27") (pintype "bidirectional"))
    )
    (net (code "73") (name "P23") (class "Default")
      (node (ref "J3") (pin "11") (pinfunction "11_11") (pintype "passive"))
      (node (ref "U3") (pin "28") (pinfunction "P0.23_28") (pintype "bidirectional"))
    )
    (net (code "74") (name "P24") (class "Default")
      (node (ref "J3") (pin "10") (pinfunction "10_10") (pintype "passive"))
      (node (ref "U3") (pin "29") (pinfunction "P0.24_29") (pintype "bidirectional"))
    )
    (net (code "75") (name "P25") (class "Default")
      (node (ref "J3") (pin "9") (pinfunction "9_9") (pintype "passive"))
      (node (ref "U3") (pin "37") (pinfunction "P0.25_37") (pintype "bidirectional"))
    )
    (net (code "76") (name "P26") (class "Default")
      (node (ref "J1") (pin "3") (pinfunction "TXO_3") (pintype "passive"))
      (node (ref "U3") (pin "38") (pinfunction "P0.26_38") (pintype "bidirectional"))
    )
    (net (code "77") (name "P27") (class "Default")
      (node (ref "J1") (pin "2") (pinfunction "RXI_2") (pintype "passive"))
      (node (ref "U3") (pin "39") (pinfunction "P0.27_39") (pintype "bidirectional"))
    )
    (net (code "78") (name "P28") (class "Default")
      (node (ref "J3") (pin "8") (pinfunction "8_8") (pintype "passive"))
      (node (ref "U3") (pin "40") (pinfunction "P0.28/AIN4_40") (pintype "bidirectional"))
    )
    (net (code "79") (name "P29") (class "Default")
      (node (ref "J3") (pin "7") (pinfunction "7_7") (pintype "passive"))
      (node (ref "U3") (pin "41") (pinfunction "P0.29/AIN5_41") (pintype "bidirectional"))
    )
    (net (code "80") (name "P30") (class "Default")
      (node (ref "J3") (pin "6") (pinfunction "6_6") (pintype "passive"))
      (node (ref "U3") (pin "42") (pinfunction "P0.30/AIN6_42") (pintype "bidirectional"))
    )
    (net (code "81") (name "P31") (class "Default")
      (node (ref "J3") (pin "5") (pinfunction "5_5") (pintype "passive"))
      (node (ref "U3") (pin "43") (pinfunction "P0.31/AIN7_43") (pintype "bidirectional"))
    )
    (net (code "82") (name "SCL") (class "Default")
      (node (ref "JP2") (pin "4") (pinfunction "4_4") (pintype "passive"))
      (node (ref "R9") (pin "1") (pinfunction "1_1") (pintype "passive"))
      (node (ref "U2") (pin "2") (pinfunction "SCL/SPC_2") (pintype "bidirectional"))
    )
    (net (code "83") (name "SDA") (class "Default")
      (node (ref "JP2") (pin "3") (pinfunction "3_3") (pintype "passive"))
      (node (ref "R8") (pin "1") (pinfunction "1_1") (pintype "passive"))
      (node (ref "U2") (pin "4") (pinfunction "SDA/SDI/SDO_4") (pintype "bidirectional"))
    )
    (net (code "84") (name "SDO_A{slash}G") (class "Default")
      (node (ref "JP3") (pin "1") (pinfunction "1_1") (pintype "passive"))
      (node (ref "R3") (pin "1") (pinfunction "1_1") (pintype "passive"))
      (node (ref "U2") (pin "5") (pinfunction "SDO_A/G_5") (pintype "bidirectional"))
    )
    (net (code "85") (name "SDO_M") (class "Default")
      (node (ref "JP3") (pin "2") (pinfunction "2_2") (pintype "passive"))
      (node (ref "R7") (pin "1") (pinfunction "1_1") (pintype "passive"))
      (node (ref "U2") (pin "6") (pinfunction "SDO_M_6") (pintype "bidirectional"))
    )
    (net (code "86") (name "SWDCLK") (class "Default")
      (node (ref "J5") (pin "4") (pinfunction "SWDCLK/TCK_4") (pintype "bidirectional"))
      (node (ref "TP2") (pin "P$1") (pinfunction "1_P$1") (pintype "bidirectional"))
      (node (ref "U3") (pin "25") (pinfunction "SWDCLK_25") (pintype "bidirectional"))
    )
    (net (code "87") (name "SWDIO") (class "Default")
      (node (ref "J5") (pin "2") (pinfunction "SWDIO/TMS_2") (pintype "bidirectional"))
      (node (ref "TP1") (pin "P$1") (pinfunction "1_P$1") (pintype "bidirectional"))
      (node (ref "U3") (pin "26") (pinfunction "SWDIO_26") (pintype "bidirectional"))
    )
    (net (code "88") (name "VCC") (class "Default")
      (node (ref "C25") (pin "1") (pinfunction "1_1") (pintype "passive"))
      (node (ref "C28") (pin "1") (pinfunction "1_1") (pintype "passive"))
      (node (ref "C6") (pin "1") (pinfunction "1_1") (pintype "passive"))
      (node (ref "J6") (pin "2") (pinfunction "2_2") (pintype "passive"))
      (node (ref "JP1") (pin "2") (pinfunction "+_2") (pintype "bidirectional"))
      (node (ref "JP8") (pin "2") (pinfunction "2_2") (pintype "passive"))
      (node (ref "Q1") (pin "2") (pinfunction "E_2") (pintype "passive"))
      (node (ref "R16") (pin "2") (pinfunction "2_2") (pintype "passive"))
      (node (ref "U1") (pin "3") (pinfunction "VBAT_3") (pintype "power_in"))
      (node (ref "U5") (pin "1") (pinfunction "VSUP_1") (pintype "bidirectional"))
    )
    (net (code "89") (name "VDD") (class "Default")
      (node (ref "C15") (pin "1") (pinfunction "1_1") (pintype "passive"))
      (node (ref "C16") (pin "1") (pinfunction "1_1") (pintype "passive"))
      (node (ref "C17") (pin "1") (pinfunction "1_1") (pintype "passive"))
      (node (ref "C2") (pin "1") (pinfunction "1_1") (pintype "passive"))
      (node (ref "C21") (pin "1") (pinfunction "1_1") (pintype "passive"))
      (node (ref "C3") (pin "1") (pinfunction "1_1") (pintype "passive"))
      (node (ref "C31") (pin "1") (pinfunction "1_1") (pintype "passive"))
      (node (ref "C7") (pin "1") (pinfunction "1_1") (pintype "passive"))
      (node (ref "D1") (pin "A") (pinfunction "A_A") (pintype "passive"))
      (node (ref "J3") (pin "3") (pinfunction "3_3") (pintype "passive"))
      (node (ref "J4") (pin "3") (pinfunction "3_3") (pintype "passive"))
      (node (ref "J5") (pin "1") (pinfunction "VCC_1") (pintype "bidirectional"))
      (node (ref "J6") (pin "1") (pinfunction "1_1") (pintype "passive"))
      (node (ref "JP2") (pin "2") (pinfunction "2_2") (pintype "passive"))
      (node (ref "JP6") (pin "2") (pinfunction "2_2") (pintype "passive"))
      (node (ref "R10") (pin "2") (pinfunction "2_2") (pintype "passive"))
      (node (ref "SJ1") (pin "2") (pinfunction "2_2") (pintype "passive"))
      (node (ref "SJ2") (pin "2") (pinfunction "2_2") (pintype "passive"))
      (node (ref "SJ3") (pin "2") (pinfunction "2_2") (pintype "passive"))
      (node (ref "U2") (pin "1") (pinfunction "VDDIO_1") (pintype "bidirectional"))
      (node (ref "U2") (pin "22") (pinfunction "VDD_22") (pintype "bidirectional"))
      (node (ref "U2") (pin "23") (pinfunction "VDD_23") (pintype "bidirectional"))
      (node (ref "U2") (pin "3") (pinfunction "VDDIO_3") (pintype "bidirectional"))
      (node (ref "U3") (pin "13") (pinfunction "VDD_13") (pintype "bidirectional"))
      (node (ref "U3") (pin "36") (pinfunction "VDD_36") (pintype "bidirectional"))
      (node (ref "U3") (pin "48") (pinfunction "VDD_48") (pintype "bidirectional"))
      (node (ref "U4") (pin "5") (pinfunction "OUT_5") (pintype "passive"))
      (node (ref "U5") (pin "16") (pinfunction "DVDD_16") (pintype "bidirectional"))
    )
    (net (code "90") (name "VIN") (class "Default")
      (node (ref "C20") (pin "1") (pinfunction "1_1") (pintype "passive"))
      (node (ref "C5") (pin "1") (pinfunction "1_1") (pintype "passive"))
      (node (ref "J3") (pin "2") (pinfunction "2_2") (pintype "passive"))
      (node (ref "J4") (pin "2") (pinfunction "2_2") (pintype "passive"))
      (node (ref "JP9") (pin "VBUS1") (pinfunction "VBUS_VBUS1") (pintype "bidirectional"))
      (node (ref "R4") (pin "2") (pinfunction "2_2") (pintype "passive"))
      (node (ref "U1") (pin "4") (pinfunction "VIN_4") (pintype "power_in"))
      (node (ref "U4") (pin "1") (pinfunction "IN_1") (pintype "input"))
      (node (ref "U4") (pin "3") (pinfunction "EN_3") (pintype "input"))
    )
    (net (code "91") (name "unconnected-(J1-CTS-Pad5)") (class "Default")
      (node (ref "J1") (pin "5") (pinfunction "CTS_5") (pintype "passive"))
    )
    (net (code "92") (name "unconnected-(J1-DTR-Pad1)") (class "Default")
      (node (ref "J1") (pin "1") (pinfunction "DTR_1") (pintype "passive"))
    )
    (net (code "93") (name "unconnected-(J5-KEY-Pad7)") (class "Default")
      (node (ref "J5") (pin "7") (pinfunction "KEY_7") (pintype "bidirectional"))
    )
    (net (code "94") (name "unconnected-(J5-NC{slash}TDI-Pad8)") (class "Default")
      (node (ref "J5") (pin "8") (pinfunction "NC/TDI_8") (pintype "bidirectional"))
    )
    (net (code "95") (name "unconnected-(JP1-PAD1-PadNC1)") (class "Default")
      (node (ref "JP1") (pin "NC1") (pinfunction "PAD1_NC1") (pintype "bidirectional"))
    )
    (net (code "96") (name "unconnected-(JP1-PAD2-PadNC2)") (class "Default")
      (node (ref "JP1") (pin "NC2") (pinfunction "PAD2_NC2") (pintype "bidirectional"))
    )
    (net (code "97") (name "unconnected-(JP9-D+-PadD+1)") (class "Default")
      (node (ref "JP9") (pin "D+1") (pinfunction "D+_D+1") (pintype "bidirectional"))
    )
    (net (code "98") (name "unconnected-(JP9-D--PadD-1)") (class "Default")
      (node (ref "JP9") (pin "D-1") (pinfunction "D-_D-1") (pintype "bidirectional"))
    )
    (net (code "99") (name "unconnected-(JP9-USBID-PadID1)") (class "Default")
      (node (ref "JP9") (pin "ID1") (pinfunction "USBID_ID1") (pintype "bidirectional"))
    )
    (net (code "100") (name "unconnected-(U$1-5.5V-Pad5V)") (class "Default")
      (node (ref "U$1") (pin "5V") (pinfunction "5.5V_5V") (pintype "bidirectional"))
    )
    (net (code "101") (name "unconnected-(U$1-GND2-PadGND1)") (class "Default")
      (node (ref "U$1") (pin "GND1") (pinfunction "GND2_GND1") (pintype "bidirectional"))
    )
    (net (code "102") (name "unconnected-(U$1-Pad3.3V)") (class "Default")
      (node (ref "U$1") (pin "3.3V") (pinfunction "3.3V_3.3V") (pintype "bidirectional"))
    )
    (net (code "103") (name "unconnected-(U$1-PadA0)") (class "Default")
      (node (ref "U$1") (pin "A0") (pinfunction "A0_A0") (pintype "bidirectional"))
    )
    (net (code "104") (name "unconnected-(U$1-PadA1)") (class "Default")
      (node (ref "U$1") (pin "A1") (pinfunction "A1_A1") (pintype "bidirectional"))
    )
    (net (code "105") (name "unconnected-(U$1-PadA2)") (class "Default")
      (node (ref "U$1") (pin "A2") (pinfunction "A2_A2") (pintype "bidirectional"))
    )
    (net (code "106") (name "unconnected-(U$1-PadA3)") (class "Default")
      (node (ref "U$1") (pin "A3") (pinfunction "A3_A3") (pintype "bidirectional"))
    )
    (net (code "107") (name "unconnected-(U$1-PadA4)") (class "Default")
      (node (ref "U$1") (pin "A4") (pinfunction "A4_A4") (pintype "bidirectional"))
    )
    (net (code "108") (name "unconnected-(U$1-PadA5)") (class "Default")
      (node (ref "U$1") (pin "A5") (pinfunction "A5_A5") (pintype "bidirectional"))
    )
    (net (code "109") (name "unconnected-(U$1-PadA6)") (class "Default")
      (node (ref "U$1") (pin "A6") (pinfunction "A6_A6") (pintype "bidirectional"))
    )
    (net (code "110") (name "unconnected-(U$1-PadA7)") (class "Default")
      (node (ref "U$1") (pin "A7") (pinfunction "A7_A7") (pintype "bidirectional"))
    )
    (net (code "111") (name "unconnected-(U$1-PadAREF)") (class "Default")
      (node (ref "U$1") (pin "AREF") (pinfunction "AREF_AREF") (pintype "bidirectional"))
    )
    (net (code "112") (name "unconnected-(U$1-PadD2)") (class "Default")
      (node (ref "U$1") (pin "D2") (pinfunction "D2_D2") (pintype "bidirectional"))
    )
    (net (code "113") (name "unconnected-(U$1-PadD3)") (class "Default")
      (node (ref "U$1") (pin "D3") (pinfunction "D3_D3") (pintype "bidirectional"))
    )
    (net (code "114") (name "unconnected-(U$1-PadD4)") (class "Default")
      (node (ref "U$1") (pin "D4") (pinfunction "D4_D4") (pintype "bidirectional"))
    )
    (net (code "115") (name "unconnected-(U$1-PadD5)") (class "Default")
      (node (ref "U$1") (pin "D5") (pinfunction "D5_D5") (pintype "bidirectional"))
    )
    (net (code "116") (name "unconnected-(U$1-PadD6)") (class "Default")
      (node (ref "U$1") (pin "D6") (pinfunction "D6_D6") (pintype "bidirectional"))
    )
    (net (code "117") (name "unconnected-(U$1-PadD7)") (class "Default")
      (node (ref "U$1") (pin "D7") (pinfunction "D7_D7") (pintype "bidirectional"))
    )
    (net (code "118") (name "unconnected-(U$1-PadD8)") (class "Default")
      (node (ref "U$1") (pin "D8") (pinfunction "D8_D8") (pintype "bidirectional"))
    )
    (net (code "119") (name "unconnected-(U$1-PadD9)") (class "Default")
      (node (ref "U$1") (pin "D9") (pinfunction "D9_D9") (pintype "bidirectional"))
    )
    (net (code "120") (name "unconnected-(U$1-PadD10)") (class "Default")
      (node (ref "U$1") (pin "D10") (pinfunction "D10_D10") (pintype "bidirectional"))
    )
    (net (code "121") (name "unconnected-(U$1-PadD11)") (class "Default")
      (node (ref "U$1") (pin "D11") (pinfunction "D11_D11") (pintype "bidirectional"))
    )
    (net (code "122") (name "unconnected-(U$1-PadD12)") (class "Default")
      (node (ref "U$1") (pin "D12") (pinfunction "D12_D12") (pintype "bidirectional"))
    )
    (net (code "123") (name "unconnected-(U$1-PadD13)") (class "Default")
      (node (ref "U$1") (pin "D13") (pinfunction "D13_D13") (pintype "bidirectional"))
    )
    (net (code "124") (name "unconnected-(U$1-PadGND)") (class "Default")
      (node (ref "U$1") (pin "GND") (pinfunction "GND_GND") (pintype "bidirectional"))
    )
    (net (code "125") (name "unconnected-(U$1-PadICSP1)") (class "Default")
      (node (ref "U$1") (pin "ICSP1") (pinfunction "ICSP1_ICSP1") (pintype "bidirectional"))
    )
    (net (code "126") (name "unconnected-(U$1-PadICSP2)") (class "Default")
      (node (ref "U$1") (pin "ICSP2") (pinfunction "ICSP2_ICSP2") (pintype "bidirectional"))
    )
    (net (code "127") (name "unconnected-(U$1-PadICSP3)") (class "Default")
      (node (ref "U$1") (pin "ICSP3") (pinfunction "ICSP3_ICSP3") (pintype "bidirectional"))
    )
    (net (code "128") (name "unconnected-(U$1-PadICSP4)") (class "Default")
      (node (ref "U$1") (pin "ICSP4") (pinfunction "ICSP4_ICSP4") (pintype "bidirectional"))
    )
    (net (code "129") (name "unconnected-(U$1-PadICSP5)") (class "Default")
      (node (ref "U$1") (pin "ICSP5") (pinfunction "ICSP5_ICSP5") (pintype "bidirectional"))
    )
    (net (code "130") (name "unconnected-(U$1-PadICSP6)") (class "Default")
      (node (ref "U$1") (pin "ICSP6") (pinfunction "ICSP6_ICSP6") (pintype "bidirectional"))
    )
    (net (code "131") (name "unconnected-(U$1-PadRAW)") (class "Default")
      (node (ref "U$1") (pin "RAW") (pinfunction "RAW_RAW") (pintype "bidirectional"))
    )
    (net (code "132") (name "unconnected-(U$1-PadRST)") (class "Default")
      (node (ref "U$1") (pin "RST") (pinfunction "RST_RST") (pintype "bidirectional"))
    )
    (net (code "133") (name "unconnected-(U$1-PadRST1)") (class "Default")
      (node (ref "U$1") (pin "RST1") (pinfunction "RST1_RST1") (pintype "bidirectional"))
    )
    (net (code "134") (name "unconnected-(U$1-PadRX1)") (class "Default")
      (node (ref "U$1") (pin "RX1") (pinfunction "RX1_RX1") (pintype "bidirectional"))
    )
    (net (code "135") (name "unconnected-(U$1-PadTX0)") (class "Default")
      (node (ref "U$1") (pin "TX0") (pinfunction "TX0_TX0") (pintype "bidirectional"))
    )
    (net (code "136") (name "unconnected-(U3-DCC-Pad47)") (class "Default")
      (node (ref "U3") (pin "47") (pinfunction "DCC_47") (pintype "bidirectional"))
    )
    (net (code "137") (name "unconnected-(U3-NC-Pad44)") (class "Default")
      (node (ref "U3") (pin "44") (pinfunction "NC_44") (pintype "bidirectional"))
    )
    (net (code "138") (name "unconnected-(U4-NC-Pad4)") (class "Default")
      (node (ref "U4") (pin "4") (pinfunction "NC_4") (pintype "input"))
    )
    (net (code "139") (name "unconnected-(U5-XO-Pad13)") (class "Default")
      (node (ref "U5") (pin "13") (pinfunction "XO_13") (pintype "bidirectional"))
    )
  )
)
